# LightSwitch.net
KiCad netlist of a schematic drawn in EAGLE
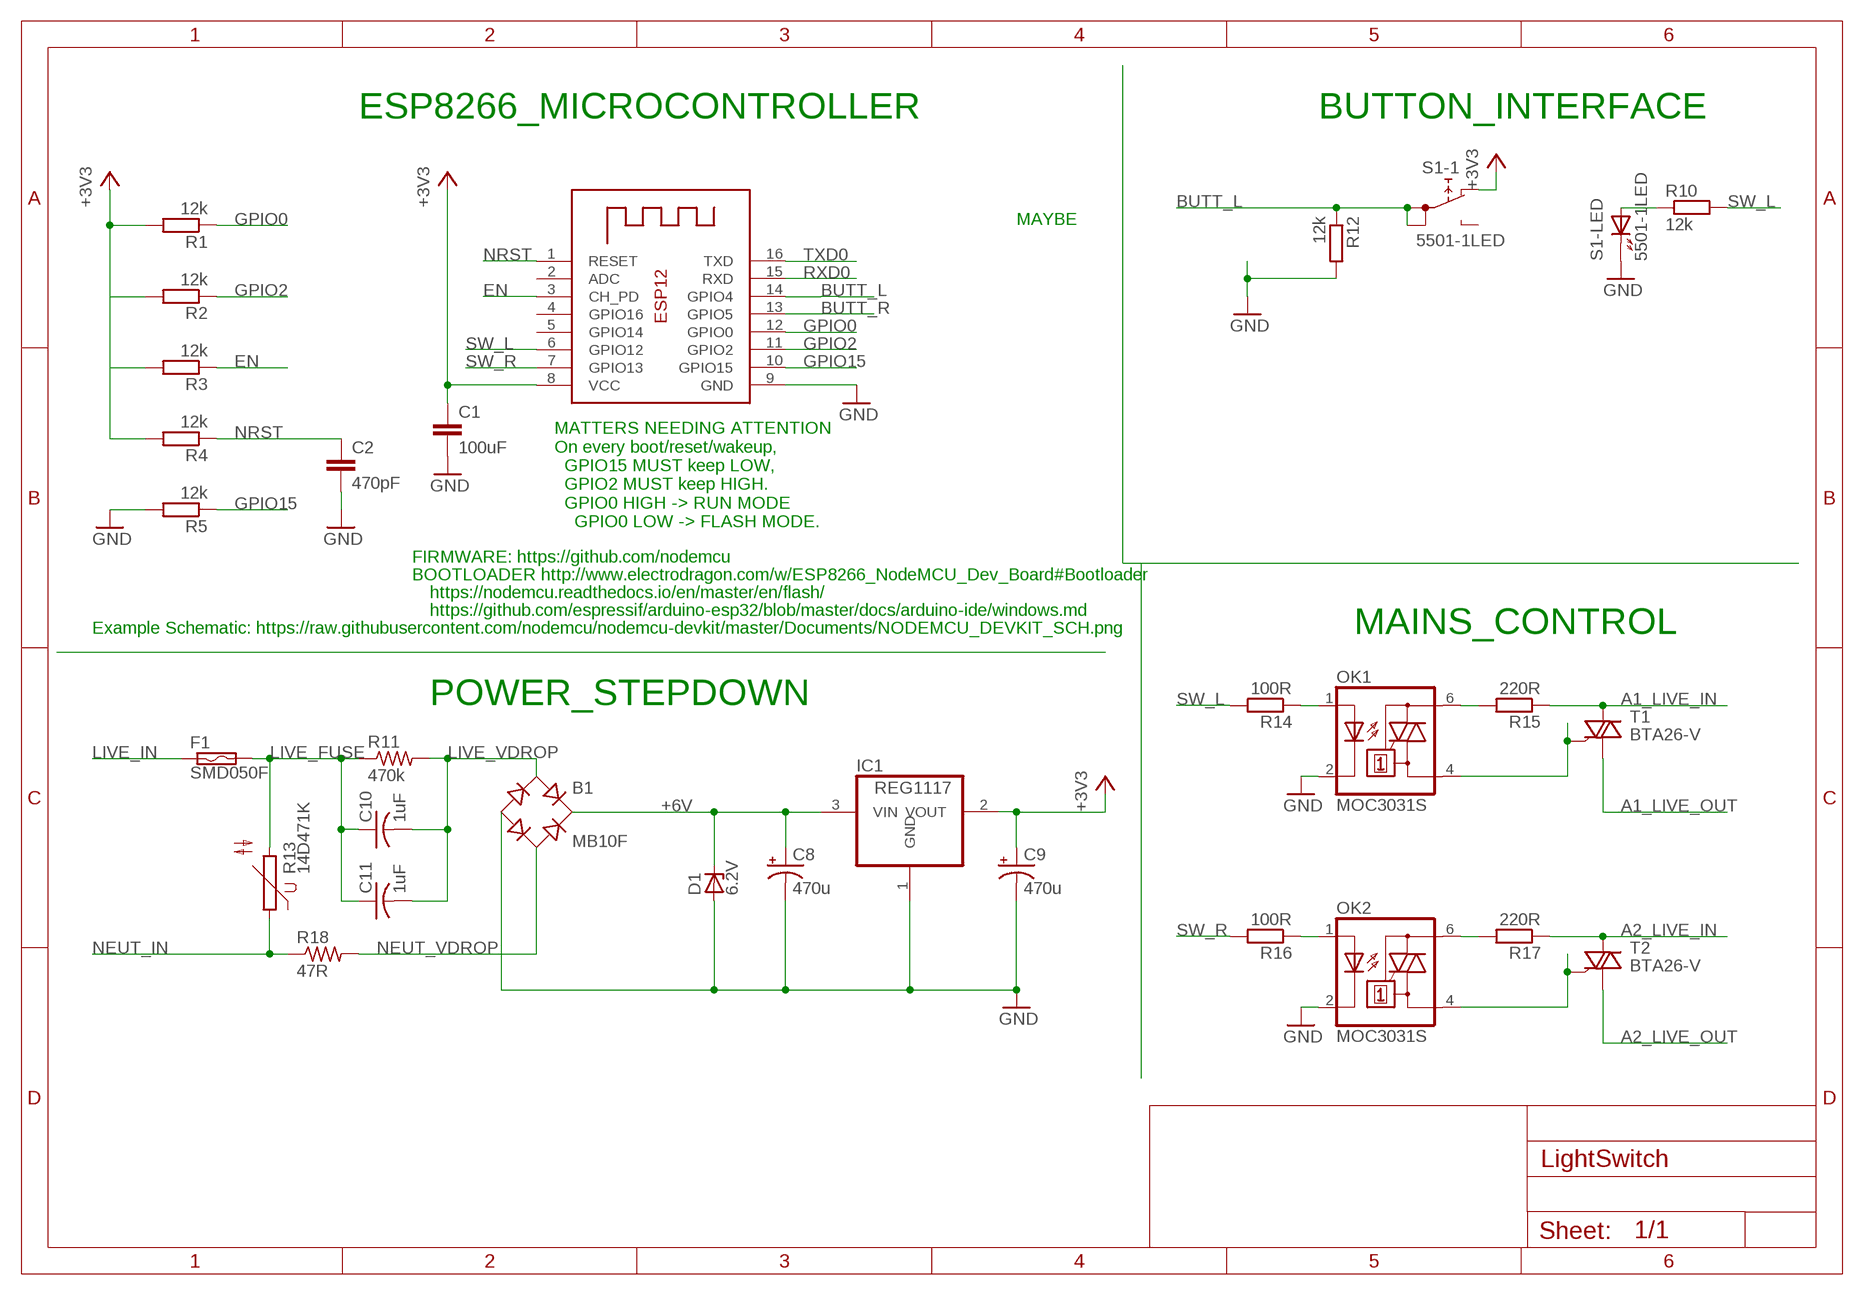
[diagram p0: schematic, sheet 1]

(export (version "E")
  (design (tool "Eeschema 10.0.6"))
  (components
    (comp (ref "B1")
      (value "MB10F")
      (footprint "eagle-import:SOIC-4")
      (libsource (lib "eagle-import") (part "MBS8"))
    )
    (comp (ref "C1")
      (value "100uF")
      (footprint "eagle-import:C0805K")
      (libsource (lib "eagle-import") (part "C-EUC0805K"))
    )
    (comp (ref "C2")
      (value "470pF")
      (footprint "eagle-import:C0805K")
      (libsource (lib "eagle-import") (part "C-EUC0805K"))
    )
    (comp (ref "C8")
      (value "470u")
      (footprint "eagle-import:E3,5-8")
      (libsource (lib "eagle-import") (part "CPOL-USE3.5-8"))
    )
    (comp (ref "C9")
      (value "470u")
      (footprint "eagle-import:E3,5-8")
      (libsource (lib "eagle-import") (part "CPOL-USE3.5-8"))
    )
    (comp (ref "C10")
      (value "1uF")
      (footprint "eagle-import:C225-074X268")
      (libsource (lib "eagle-import") (part "C-US225-074X268"))
    )
    (comp (ref "C11")
      (value "1uF")
      (footprint "eagle-import:C225-074X268")
      (libsource (lib "eagle-import") (part "C-US225-074X268"))
    )
    (comp (ref "D1")
      (value "6.2V")
      (footprint "eagle-import:SMB")
      (libsource (lib "eagle-import") (part "ZENER-DIODESMB"))
    )
    (comp (ref "F1")
      (value "SMD050F")
      (footprint "eagle-import:SMD050F")
      (libsource (lib "eagle-import") (part "SMDF050"))
    )
    (comp (ref "IC1")
      (value "REG1117")
      (footprint "eagle-import:SOT223")
      (libsource (lib "eagle-import") (part "REG1117"))
    )
    (comp (ref "OK1")
      (value "MOC3031S")
      (footprint "eagle-import:DIL6-SMD")
      (fields (field (name "MF") "FAIRCHILD SEMICONDUCTOR") (field (name "MPN") "MOC3031SM"))
      (libsource (lib "eagle-import") (part "MOC30S31"))
    )
    (comp (ref "OK2")
      (value "MOC3031S")
      (footprint "eagle-import:DIL6-SMD")
      (fields (field (name "MF") "FAIRCHILD SEMICONDUCTOR") (field (name "MPN") "MOC3031SM"))
      (libsource (lib "eagle-import") (part "MOC30S31"))
    )
    (comp (ref "R1")
      (value "12k")
      (footprint "eagle-import:M0805")
      (libsource (lib "eagle-import") (part "R-EU_M0805"))
    )
    (comp (ref "R2")
      (value "12k")
      (footprint "eagle-import:M0805")
      (libsource (lib "eagle-import") (part "R-EU_M0805"))
    )
    (comp (ref "R3")
      (value "12k")
      (footprint "eagle-import:M0805")
      (libsource (lib "eagle-import") (part "R-EU_M0805"))
    )
    (comp (ref "R4")
      (value "12k")
      (footprint "eagle-import:M0805")
      (libsource (lib "eagle-import") (part "R-EU_M0805"))
    )
    (comp (ref "R5")
      (value "12k")
      (footprint "eagle-import:M0805")
      (libsource (lib "eagle-import") (part "R-EU_M0805"))
    )
    (comp (ref "R10")
      (value "12k")
      (footprint "eagle-import:M0805")
      (libsource (lib "eagle-import") (part "R-EU_M0805"))
    )
    (comp (ref "R11")
      (value "470k")
      (footprint "eagle-import:0309_12")
      (libsource (lib "eagle-import") (part "R-US_0309/12"))
    )
    (comp (ref "R12")
      (value "12k")
      (footprint "eagle-import:M0805")
      (libsource (lib "eagle-import") (part "R-EU_M0805"))
    )
    (comp (ref "R13")
      (value "14D471K")
      (footprint "eagle-import:S07K40")
      (libsource (lib "eagle-import") (part "S07K40"))
    )
    (comp (ref "R14")
      (value "100R")
      (footprint "eagle-import:M0805")
      (libsource (lib "eagle-import") (part "R-EU_M0805"))
    )
    (comp (ref "R15")
      (value "220R")
      (footprint "eagle-import:M0805")
      (libsource (lib "eagle-import") (part "R-EU_M0805"))
    )
    (comp (ref "R16")
      (value "100R")
      (footprint "eagle-import:M0805")
      (libsource (lib "eagle-import") (part "R-EU_M0805"))
    )
    (comp (ref "R17")
      (value "220R")
      (footprint "eagle-import:M0805")
      (libsource (lib "eagle-import") (part "R-EU_M0805"))
    )
    (comp (ref "R18")
      (value "47R")
      (footprint "eagle-import:0309_12")
      (libsource (lib "eagle-import") (part "R-US_0309/12"))
    )
    (comp (ref "S1")
      (value "5501-1LED")
      (footprint "eagle-import:5501-1LED")
      (libsource (lib "eagle-import") (part "55?-1LED01"))
    )
    (comp (ref "T1")
      (value "BTA26-V")
      (footprint "eagle-import:TOP3S-1")
      (libsource (lib "eagle-import") (part "BTA26-V"))
    )
    (comp (ref "T2")
      (value "BTA26-V")
      (footprint "eagle-import:TOP3S-1")
      (libsource (lib "eagle-import") (part "BTA26-V"))
    )
    (comp (ref "X1")
      (value "ESP-12")
      (footprint "eagle-import:ESP-12")
      (libsource (lib "eagle-import") (part "ESP-12"))
    )
  )
  (nets
    (net (code "1") (name "+3V3") (class "Default")
      (node (ref "C1") (pin "1") (pinfunction "1_1") (pintype "passive"))
      (node (ref "C9") (pin "+") (pinfunction "+_+") (pintype "passive"))
      (node (ref "IC1") (pin "2") (pinfunction "VOUT_2") (pintype "output"))
      (node (ref "R1") (pin "2") (pinfunction "2_2") (pintype "passive"))
      (node (ref "R4") (pin "2") (pinfunction "2_2") (pintype "passive"))
      (node (ref "S1") (pin "NC") (pinfunction "NC_NC") (pintype "passive"))
      (node (ref "X1") (pin "8") (pinfunction "VCC_8") (pintype "power_in"))
    )
    (net (code "2") (name "/+6V") (class "Default")
      (node (ref "B1") (pin "+") (pinfunction "+_+") (pintype "passive"))
      (node (ref "C8") (pin "+") (pinfunction "+_+") (pintype "passive"))
      (node (ref "D1") (pin "C") (pinfunction "C_C") (pintype "passive"))
      (node (ref "IC1") (pin "3") (pinfunction "VIN_3") (pintype "input"))
    )
    (net (code "3") (name "/A1_LIVE_IN") (class "Default")
      (node (ref "R15") (pin "1") (pinfunction "1_1") (pintype "passive"))
      (node (ref "T1") (pin "A2") (pinfunction "A2_A2") (pintype "passive"))
    )
    (net (code "4") (name "/A1_LIVE_OUT") (class "Default")
      (node (ref "T1") (pin "A1") (pinfunction "A1_A1") (pintype "passive"))
    )
    (net (code "5") (name "/A2_LIVE_IN") (class "Default")
      (node (ref "R17") (pin "1") (pinfunction "1_1") (pintype "passive"))
      (node (ref "T2") (pin "A2") (pinfunction "A2_A2") (pintype "passive"))
    )
    (net (code "6") (name "/A2_LIVE_OUT") (class "Default")
      (node (ref "T2") (pin "A1") (pinfunction "A1_A1") (pintype "passive"))
    )
    (net (code "7") (name "/BUTT_L") (class "Default")
      (node (ref "R12") (pin "1") (pinfunction "1_1") (pintype "passive"))
      (node (ref "S1") (pin "1A") (pinfunction "1A_1A") (pintype "passive"))
      (node (ref "S1") (pin "1B") (pinfunction "1B_1B") (pintype "passive"))
      (node (ref "X1") (pin "14") (pinfunction "GPIO4_14") (pintype "bidirectional"))
    )
    (net (code "8") (name "/BUTT_R") (class "Default")
      (node (ref "X1") (pin "13") (pinfunction "GPIO5_13") (pintype "bidirectional"))
    )
    (net (code "9") (name "/EN") (class "Default")
      (node (ref "R3") (pin "1") (pinfunction "1_1") (pintype "passive"))
      (node (ref "X1") (pin "3") (pinfunction "CH_PD_3") (pintype "input"))
    )
    (net (code "10") (name "/GPIO0") (class "Default")
      (node (ref "R1") (pin "1") (pinfunction "1_1") (pintype "passive"))
      (node (ref "X1") (pin "12") (pinfunction "GPIO0_12") (pintype "bidirectional"))
    )
    (net (code "11") (name "/GPIO2") (class "Default")
      (node (ref "R2") (pin "1") (pinfunction "1_1") (pintype "passive"))
      (node (ref "X1") (pin "11") (pinfunction "GPIO2_11") (pintype "bidirectional"))
    )
    (net (code "12") (name "/GPIO15") (class "Default")
      (node (ref "R5") (pin "1") (pinfunction "1_1") (pintype "passive"))
      (node (ref "X1") (pin "10") (pinfunction "GPIO15_10") (pintype "bidirectional"))
    )
    (net (code "13") (name "/LIVE_FUSE") (class "Default")
      (node (ref "C10") (pin "1") (pinfunction "1_1") (pintype "passive"))
      (node (ref "C11") (pin "1") (pinfunction "1_1") (pintype "passive"))
      (node (ref "F1") (pin "2") (pinfunction "2_2") (pintype "passive"))
      (node (ref "R11") (pin "1") (pinfunction "1_1") (pintype "passive"))
      (node (ref "R13") (pin "2") (pinfunction "2_2") (pintype "passive"))
    )
    (net (code "14") (name "/LIVE_IN") (class "Default")
      (node (ref "F1") (pin "1") (pinfunction "1_1") (pintype "passive"))
    )
    (net (code "15") (name "/LIVE_VDROP") (class "Default")
      (node (ref "B1") (pin "~1") (pinfunction "AC1_~1") (pintype "passive"))
      (node (ref "C10") (pin "2") (pinfunction "2_2") (pintype "passive"))
      (node (ref "C11") (pin "2") (pinfunction "2_2") (pintype "passive"))
      (node (ref "R11") (pin "2") (pinfunction "2_2") (pintype "passive"))
    )
    (net (code "16") (name "/NEUT_IN") (class "Default")
      (node (ref "R13") (pin "1") (pinfunction "1_1") (pintype "passive"))
      (node (ref "R18") (pin "1") (pinfunction "1_1") (pintype "passive"))
    )
    (net (code "17") (name "/NEUT_VDROP") (class "Default")
      (node (ref "B1") (pin "~2") (pinfunction "AC2_~2") (pintype "passive"))
      (node (ref "R18") (pin "2") (pinfunction "2_2") (pintype "passive"))
    )
    (net (code "18") (name "/NRST") (class "Default")
      (node (ref "C2") (pin "1") (pinfunction "1_1") (pintype "passive"))
      (node (ref "R4") (pin "1") (pinfunction "1_1") (pintype "passive"))
      (node (ref "X1") (pin "1") (pinfunction "RESET_1") (pintype "input"))
    )
    (net (code "19") (name "/RXD0") (class "Default")
      (node (ref "X1") (pin "15") (pinfunction "RXD_15") (pintype "input"))
    )
    (net (code "20") (name "/SW_L") (class "Default")
      (node (ref "R10") (pin "2") (pinfunction "2_2") (pintype "passive"))
      (node (ref "R14") (pin "2") (pinfunction "2_2") (pintype "passive"))
      (node (ref "X1") (pin "6") (pinfunction "GPIO12_6") (pintype "bidirectional"))
    )
    (net (code "21") (name "/SW_R") (class "Default")
      (node (ref "R16") (pin "2") (pinfunction "2_2") (pintype "passive"))
      (node (ref "X1") (pin "7") (pinfunction "GPIO13_7") (pintype "bidirectional"))
    )
    (net (code "22") (name "/TXD0") (class "Default")
      (node (ref "X1") (pin "16") (pinfunction "TXD_16") (pintype "output"))
    )
    (net (code "23") (name "GND") (class "Default")
      (node (ref "B1") (pin "-") (pinfunction "-_-") (pintype "passive"))
      (node (ref "C1") (pin "2") (pinfunction "2_2") (pintype "passive"))
      (node (ref "C2") (pin "2") (pinfunction "2_2") (pintype "passive"))
      (node (ref "C8") (pin "-") (pinfunction "-_-") (pintype "passive"))
      (node (ref "C9") (pin "-") (pinfunction "-_-") (pintype "passive"))
      (node (ref "D1") (pin "A") (pinfunction "A_A") (pintype "passive"))
      (node (ref "IC1") (pin "1") (pinfunction "GND_1") (pintype "power_in"))
      (node (ref "OK1") (pin "2") (pinfunction "C_2") (pintype "passive"))
      (node (ref "OK2") (pin "2") (pinfunction "C_2") (pintype "passive"))
      (node (ref "R12") (pin "2") (pinfunction "2_2") (pintype "passive"))
      (node (ref "R5") (pin "2") (pinfunction "2_2") (pintype "passive"))
      (node (ref "S1") (pin "-") (pinfunction "K_-") (pintype "passive"))
      (node (ref "X1") (pin "9") (pinfunction "GND_9") (pintype "power_in"))
    )
    (net (code "24") (name "Net-(OK1-A)") (class "Default")
      (node (ref "OK1") (pin "1") (pinfunction "A_1") (pintype "passive"))
      (node (ref "R14") (pin "1") (pinfunction "1_1") (pintype "passive"))
    )
    (net (code "25") (name "Net-(OK1-A1)") (class "Default")
      (node (ref "OK1") (pin "4") (pinfunction "A1_4") (pintype "passive"))
      (node (ref "T1") (pin "G") (pinfunction "G_G") (pintype "passive"))
    )
    (net (code "26") (name "Net-(OK1-A2)") (class "Default")
      (node (ref "OK1") (pin "6") (pinfunction "A2_6") (pintype "passive"))
      (node (ref "R15") (pin "2") (pinfunction "2_2") (pintype "passive"))
    )
    (net (code "27") (name "Net-(OK2-A)") (class "Default")
      (node (ref "OK2") (pin "1") (pinfunction "A_1") (pintype "passive"))
      (node (ref "R16") (pin "1") (pinfunction "1_1") (pintype "passive"))
    )
    (net (code "28") (name "Net-(OK2-A1)") (class "Default")
      (node (ref "OK2") (pin "4") (pinfunction "A1_4") (pintype "passive"))
      (node (ref "T2") (pin "G") (pinfunction "G_G") (pintype "passive"))
    )
    (net (code "29") (name "Net-(OK2-A2)") (class "Default")
      (node (ref "OK2") (pin "6") (pinfunction "A2_6") (pintype "passive"))
      (node (ref "R17") (pin "2") (pinfunction "2_2") (pintype "passive"))
    )
    (net (code "30") (name "Net-(S1B-A)") (class "Default")
      (node (ref "R10") (pin "1") (pinfunction "1_1") (pintype "passive"))
      (node (ref "S1") (pin "+") (pinfunction "A_+") (pintype "passive"))
    )
    (net (code "31") (name "unconnected-(R2-Pad2)") (class "Default")
      (node (ref "R2") (pin "2") (pinfunction "2_2") (pintype "passive"))
    )
    (net (code "32") (name "unconnected-(R3-Pad2)") (class "Default")
      (node (ref "R3") (pin "2") (pinfunction "2_2") (pintype "passive"))
    )
    (net (code "33") (name "unconnected-(S1-PadNO)") (class "Default")
      (node (ref "S1") (pin "NO") (pinfunction "NO_NO") (pintype "passive"))
    )
    (net (code "34") (name "unconnected-(X1-ADC-Pad2)") (class "Default")
      (node (ref "X1") (pin "2") (pinfunction "ADC_2") (pintype "passive"))
    )
    (net (code "35") (name "unconnected-(X1-GPIO14-Pad5)") (class "Default")
      (node (ref "X1") (pin "5") (pinfunction "GPIO14_5") (pintype "bidirectional"))
    )
    (net (code "36") (name "unconnected-(X1-GPIO16-Pad4)") (class "Default")
      (node (ref "X1") (pin "4") (pinfunction "GPIO16_4") (pintype "bidirectional"))
    )
  )
)
